# Bokskort_Minilysrelamen_top.net
KiCad netlist of a schematic drawn in Altium Designer
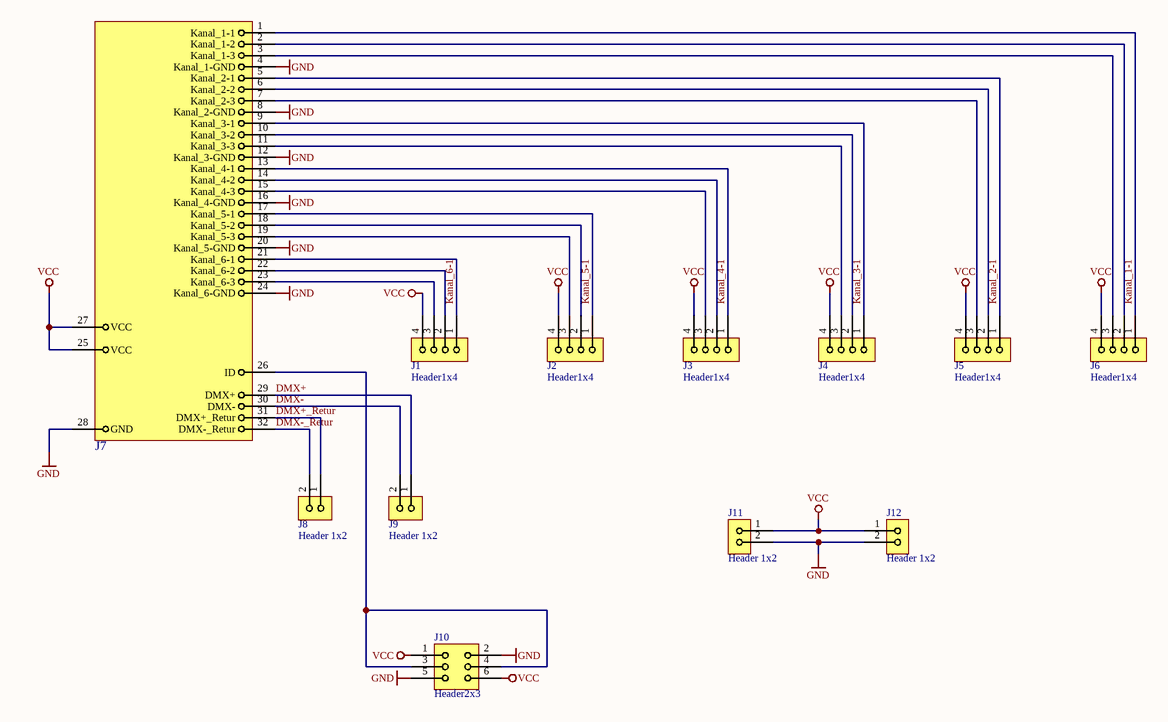
[diagram p0: Bokskort_Minilysrelamen_top.SchDoc]

(export (version "E")
  (design (tool "Eeschema 10.0.6"))
  (components
    (comp (ref "J1")
      (value "Header1x4")
      (footprint "JST_B4B-PH-K-S")
      (description "JST PH-Series 2mm Pitch")
      (libsource (lib "OVLib") (part "Header1x4"))
    )
    (comp (ref "J2")
      (value "Header1x4")
      (footprint "JST_B4B-PH-K-S")
      (description "JST PH-Series 2mm Pitch")
      (libsource (lib "OVLib") (part "Header1x4"))
    )
    (comp (ref "J3")
      (value "Header1x4")
      (footprint "JST_B4B-PH-K-S")
      (description "JST PH-Series 2mm Pitch")
      (libsource (lib "OVLib") (part "Header1x4"))
    )
    (comp (ref "J4")
      (value "Header1x4")
      (footprint "JST_B4B-PH-K-S")
      (description "JST PH-Series 2mm Pitch")
      (libsource (lib "OVLib") (part "Header1x4"))
    )
    (comp (ref "J5")
      (value "Header1x4")
      (footprint "JST_B4B-PH-K-S")
      (description "JST PH-Series 2mm Pitch")
      (libsource (lib "OVLib") (part "Header1x4"))
    )
    (comp (ref "J6")
      (value "Header1x4")
      (footprint "JST_B4B-PH-K-S")
      (description "JST PH-Series 2mm Pitch")
      (libsource (lib "OVLib") (part "Header1x4"))
    )
    (comp (ref "J7")
      (value "Lysreklameparalellbusskontakt2015_FEMALE")
      (footprint "HDRRAF32W64P254_2X16_4064X1260X600B")
      (libsource (lib "Lysreklameparalellbusskontakt2015_FEMALE") (part "Lysreklameparalellbusskontakt2015_FEMALE"))
    )
    (comp (ref "J8")
      (value "Header 1x2")
      (footprint "HDRV2W64P254_1X2_508X254X900B")
      (description "2,54mm pitch")
      (libsource (lib "OVLib") (part "Header1x2"))
    )
    (comp (ref "J9")
      (value "Header 1x2")
      (footprint "HDRV2W64P254_1X2_508X254X900B")
      (description "2,54mm pitch")
      (libsource (lib "OVLib") (part "Header1x2"))
    )
    (comp (ref "J10")
      (value "Header2x3")
      (footprint "HDRV6W64P254_2X3_762X508X900B")
      (description "2,54mm pitch")
      (libsource (lib "OVLib") (part "Header2x3"))
    )
    (comp (ref "J11")
      (value "Header 1x2")
      (footprint "HDRV2W64P254_1X2_508X254X900B")
      (description "2,54mm pitch")
      (libsource (lib "OVLib") (part "Header1x2"))
    )
    (comp (ref "J12")
      (value "Header 1x2")
      (footprint "HDRV2W64P254_1X2_508X254X900B")
      (description "2,54mm pitch")
      (libsource (lib "") (part "Header1x2_1"))
    )
  )
  (nets
    (net (code "1") (name "/DMX+") (class "Default")
      (node (ref "J7") (pin "29") (pinfunction "DMX+_29") (pintype "passive"))
      (node (ref "J9") (pin "1") (pinfunction "1_1") (pintype "passive"))
    )
    (net (code "2") (name "/DMX+_Retur") (class "Default")
      (node (ref "J7") (pin "31") (pinfunction "DMX+_Retur_31") (pintype "passive"))
      (node (ref "J8") (pin "1") (pinfunction "1_1") (pintype "passive"))
    )
    (net (code "3") (name "/DMX-") (class "Default")
      (node (ref "J7") (pin "30") (pinfunction "DMX-_30") (pintype "passive"))
      (node (ref "J9") (pin "2") (pinfunction "2_2") (pintype "passive"))
    )
    (net (code "4") (name "/DMX-_Retur") (class "Default")
      (node (ref "J7") (pin "32") (pinfunction "DMX-_Retur_32") (pintype "passive"))
      (node (ref "J8") (pin "2") (pinfunction "2_2") (pintype "passive"))
    )
    (net (code "5") (name "/Kanal_1-1") (class "Default")
      (node (ref "J6") (pin "1") (pinfunction "1_1") (pintype "passive"))
      (node (ref "J7") (pin "1") (pinfunction "Kanal_1-1_1") (pintype "passive"))
    )
    (net (code "6") (name "/Kanal_2-1") (class "Default")
      (node (ref "J5") (pin "1") (pinfunction "1_1") (pintype "passive"))
      (node (ref "J7") (pin "5") (pinfunction "Kanal_2-1_5") (pintype "passive"))
    )
    (net (code "7") (name "/Kanal_3-1") (class "Default")
      (node (ref "J4") (pin "1") (pinfunction "1_1") (pintype "passive"))
      (node (ref "J7") (pin "9") (pinfunction "Kanal_3-1_9") (pintype "passive"))
    )
    (net (code "8") (name "/Kanal_4-1") (class "Default")
      (node (ref "J3") (pin "1") (pinfunction "1_1") (pintype "passive"))
      (node (ref "J7") (pin "13") (pinfunction "Kanal_4-1_13") (pintype "passive"))
    )
    (net (code "9") (name "/Kanal_5-1") (class "Default")
      (node (ref "J2") (pin "1") (pinfunction "1_1") (pintype "passive"))
      (node (ref "J7") (pin "17") (pinfunction "Kanal_5-1_17") (pintype "passive"))
    )
    (net (code "10") (name "/Kanal_6-1") (class "Default")
      (node (ref "J1") (pin "1") (pinfunction "1_1") (pintype "passive"))
      (node (ref "J7") (pin "21") (pinfunction "Kanal_6-1_21") (pintype "passive"))
    )
    (net (code "11") (name "GND") (class "Default")
      (node (ref "J10") (pin "2") (pinfunction "2_2") (pintype "passive"))
      (node (ref "J10") (pin "5") (pinfunction "5_5") (pintype "passive"))
      (node (ref "J11") (pin "2") (pinfunction "2_2") (pintype "passive"))
      (node (ref "J12") (pin "2") (pinfunction "2_2") (pintype "passive"))
      (node (ref "J7") (pin "12") (pinfunction "Kanal_3-GND_12") (pintype "passive"))
      (node (ref "J7") (pin "16") (pinfunction "Kanal_4-GND_16") (pintype "passive"))
      (node (ref "J7") (pin "20") (pinfunction "Kanal_5-GND_20") (pintype "passive"))
      (node (ref "J7") (pin "24") (pinfunction "Kanal_6-GND_24") (pintype "passive"))
      (node (ref "J7") (pin "28") (pinfunction "GND_28") (pintype "passive"))
      (node (ref "J7") (pin "4") (pinfunction "Kanal_1-GND_4") (pintype "passive"))
      (node (ref "J7") (pin "8") (pinfunction "Kanal_2-GND_8") (pintype "passive"))
    )
    (net (code "12") (name "Net-(J7-ID)") (class "Default")
      (node (ref "J10") (pin "3") (pinfunction "3_3") (pintype "passive"))
      (node (ref "J10") (pin "4") (pinfunction "4_4") (pintype "passive"))
      (node (ref "J7") (pin "26") (pinfunction "ID_26") (pintype "passive"))
    )
    (net (code "13") (name "Net-(J7-Kanal_1-2)") (class "Default")
      (node (ref "J6") (pin "2") (pinfunction "2_2") (pintype "passive"))
      (node (ref "J7") (pin "2") (pinfunction "Kanal_1-2_2") (pintype "passive"))
    )
    (net (code "14") (name "Net-(J7-Kanal_1-3)") (class "Default")
      (node (ref "J6") (pin "3") (pinfunction "3_3") (pintype "passive"))
      (node (ref "J7") (pin "3") (pinfunction "Kanal_1-3_3") (pintype "passive"))
    )
    (net (code "15") (name "Net-(J7-Kanal_2-2)") (class "Default")
      (node (ref "J5") (pin "2") (pinfunction "2_2") (pintype "passive"))
      (node (ref "J7") (pin "6") (pinfunction "Kanal_2-2_6") (pintype "passive"))
    )
    (net (code "16") (name "Net-(J7-Kanal_2-3)") (class "Default")
      (node (ref "J5") (pin "3") (pinfunction "3_3") (pintype "passive"))
      (node (ref "J7") (pin "7") (pinfunction "Kanal_2-3_7") (pintype "passive"))
    )
    (net (code "17") (name "Net-(J7-Kanal_3-2)") (class "Default")
      (node (ref "J4") (pin "2") (pinfunction "2_2") (pintype "passive"))
      (node (ref "J7") (pin "10") (pinfunction "Kanal_3-2_10") (pintype "passive"))
    )
    (net (code "18") (name "Net-(J7-Kanal_3-3)") (class "Default")
      (node (ref "J4") (pin "3") (pinfunction "3_3") (pintype "passive"))
      (node (ref "J7") (pin "11") (pinfunction "Kanal_3-3_11") (pintype "passive"))
    )
    (net (code "19") (name "Net-(J7-Kanal_4-2)") (class "Default")
      (node (ref "J3") (pin "2") (pinfunction "2_2") (pintype "passive"))
      (node (ref "J7") (pin "14") (pinfunction "Kanal_4-2_14") (pintype "passive"))
    )
    (net (code "20") (name "Net-(J7-Kanal_4-3)") (class "Default")
      (node (ref "J3") (pin "3") (pinfunction "3_3") (pintype "passive"))
      (node (ref "J7") (pin "15") (pinfunction "Kanal_4-3_15") (pintype "passive"))
    )
    (net (code "21") (name "Net-(J7-Kanal_5-2)") (class "Default")
      (node (ref "J2") (pin "2") (pinfunction "2_2") (pintype "passive"))
      (node (ref "J7") (pin "18") (pinfunction "Kanal_5-2_18") (pintype "passive"))
    )
    (net (code "22") (name "Net-(J7-Kanal_5-3)") (class "Default")
      (node (ref "J2") (pin "3") (pinfunction "3_3") (pintype "passive"))
      (node (ref "J7") (pin "19") (pinfunction "Kanal_5-3_19") (pintype "passive"))
    )
    (net (code "23") (name "Net-(J7-Kanal_6-2)") (class "Default")
      (node (ref "J1") (pin "2") (pinfunction "2_2") (pintype "passive"))
      (node (ref "J7") (pin "22") (pinfunction "Kanal_6-2_22") (pintype "passive"))
    )
    (net (code "24") (name "Net-(J7-Kanal_6-3)") (class "Default")
      (node (ref "J1") (pin "3") (pinfunction "3_3") (pintype "passive"))
      (node (ref "J7") (pin "23") (pinfunction "Kanal_6-3_23") (pintype "passive"))
    )
    (net (code "25") (name "VCC") (class "Default")
      (node (ref "J1") (pin "4") (pinfunction "4_4") (pintype "passive"))
      (node (ref "J10") (pin "1") (pinfunction "1_1") (pintype "passive"))
      (node (ref "J10") (pin "6") (pinfunction "6_6") (pintype "passive"))
      (node (ref "J11") (pin "1") (pinfunction "1_1") (pintype "passive"))
      (node (ref "J12") (pin "1") (pinfunction "1_1") (pintype "passive"))
      (node (ref "J2") (pin "4") (pinfunction "4_4") (pintype "passive"))
      (node (ref "J3") (pin "4") (pinfunction "4_4") (pintype "passive"))
      (node (ref "J4") (pin "4") (pinfunction "4_4") (pintype "passive"))
      (node (ref "J5") (pin "4") (pinfunction "4_4") (pintype "passive"))
      (node (ref "J6") (pin "4") (pinfunction "4_4") (pintype "passive"))
      (node (ref "J7") (pin "25") (pinfunction "VCC_25") (pintype "passive"))
      (node (ref "J7") (pin "27") (pinfunction "VCC_27") (pintype "passive"))
    )
  )
)
